# FPGA.net
KiCad netlist of a schematic drawn in Altium Designer
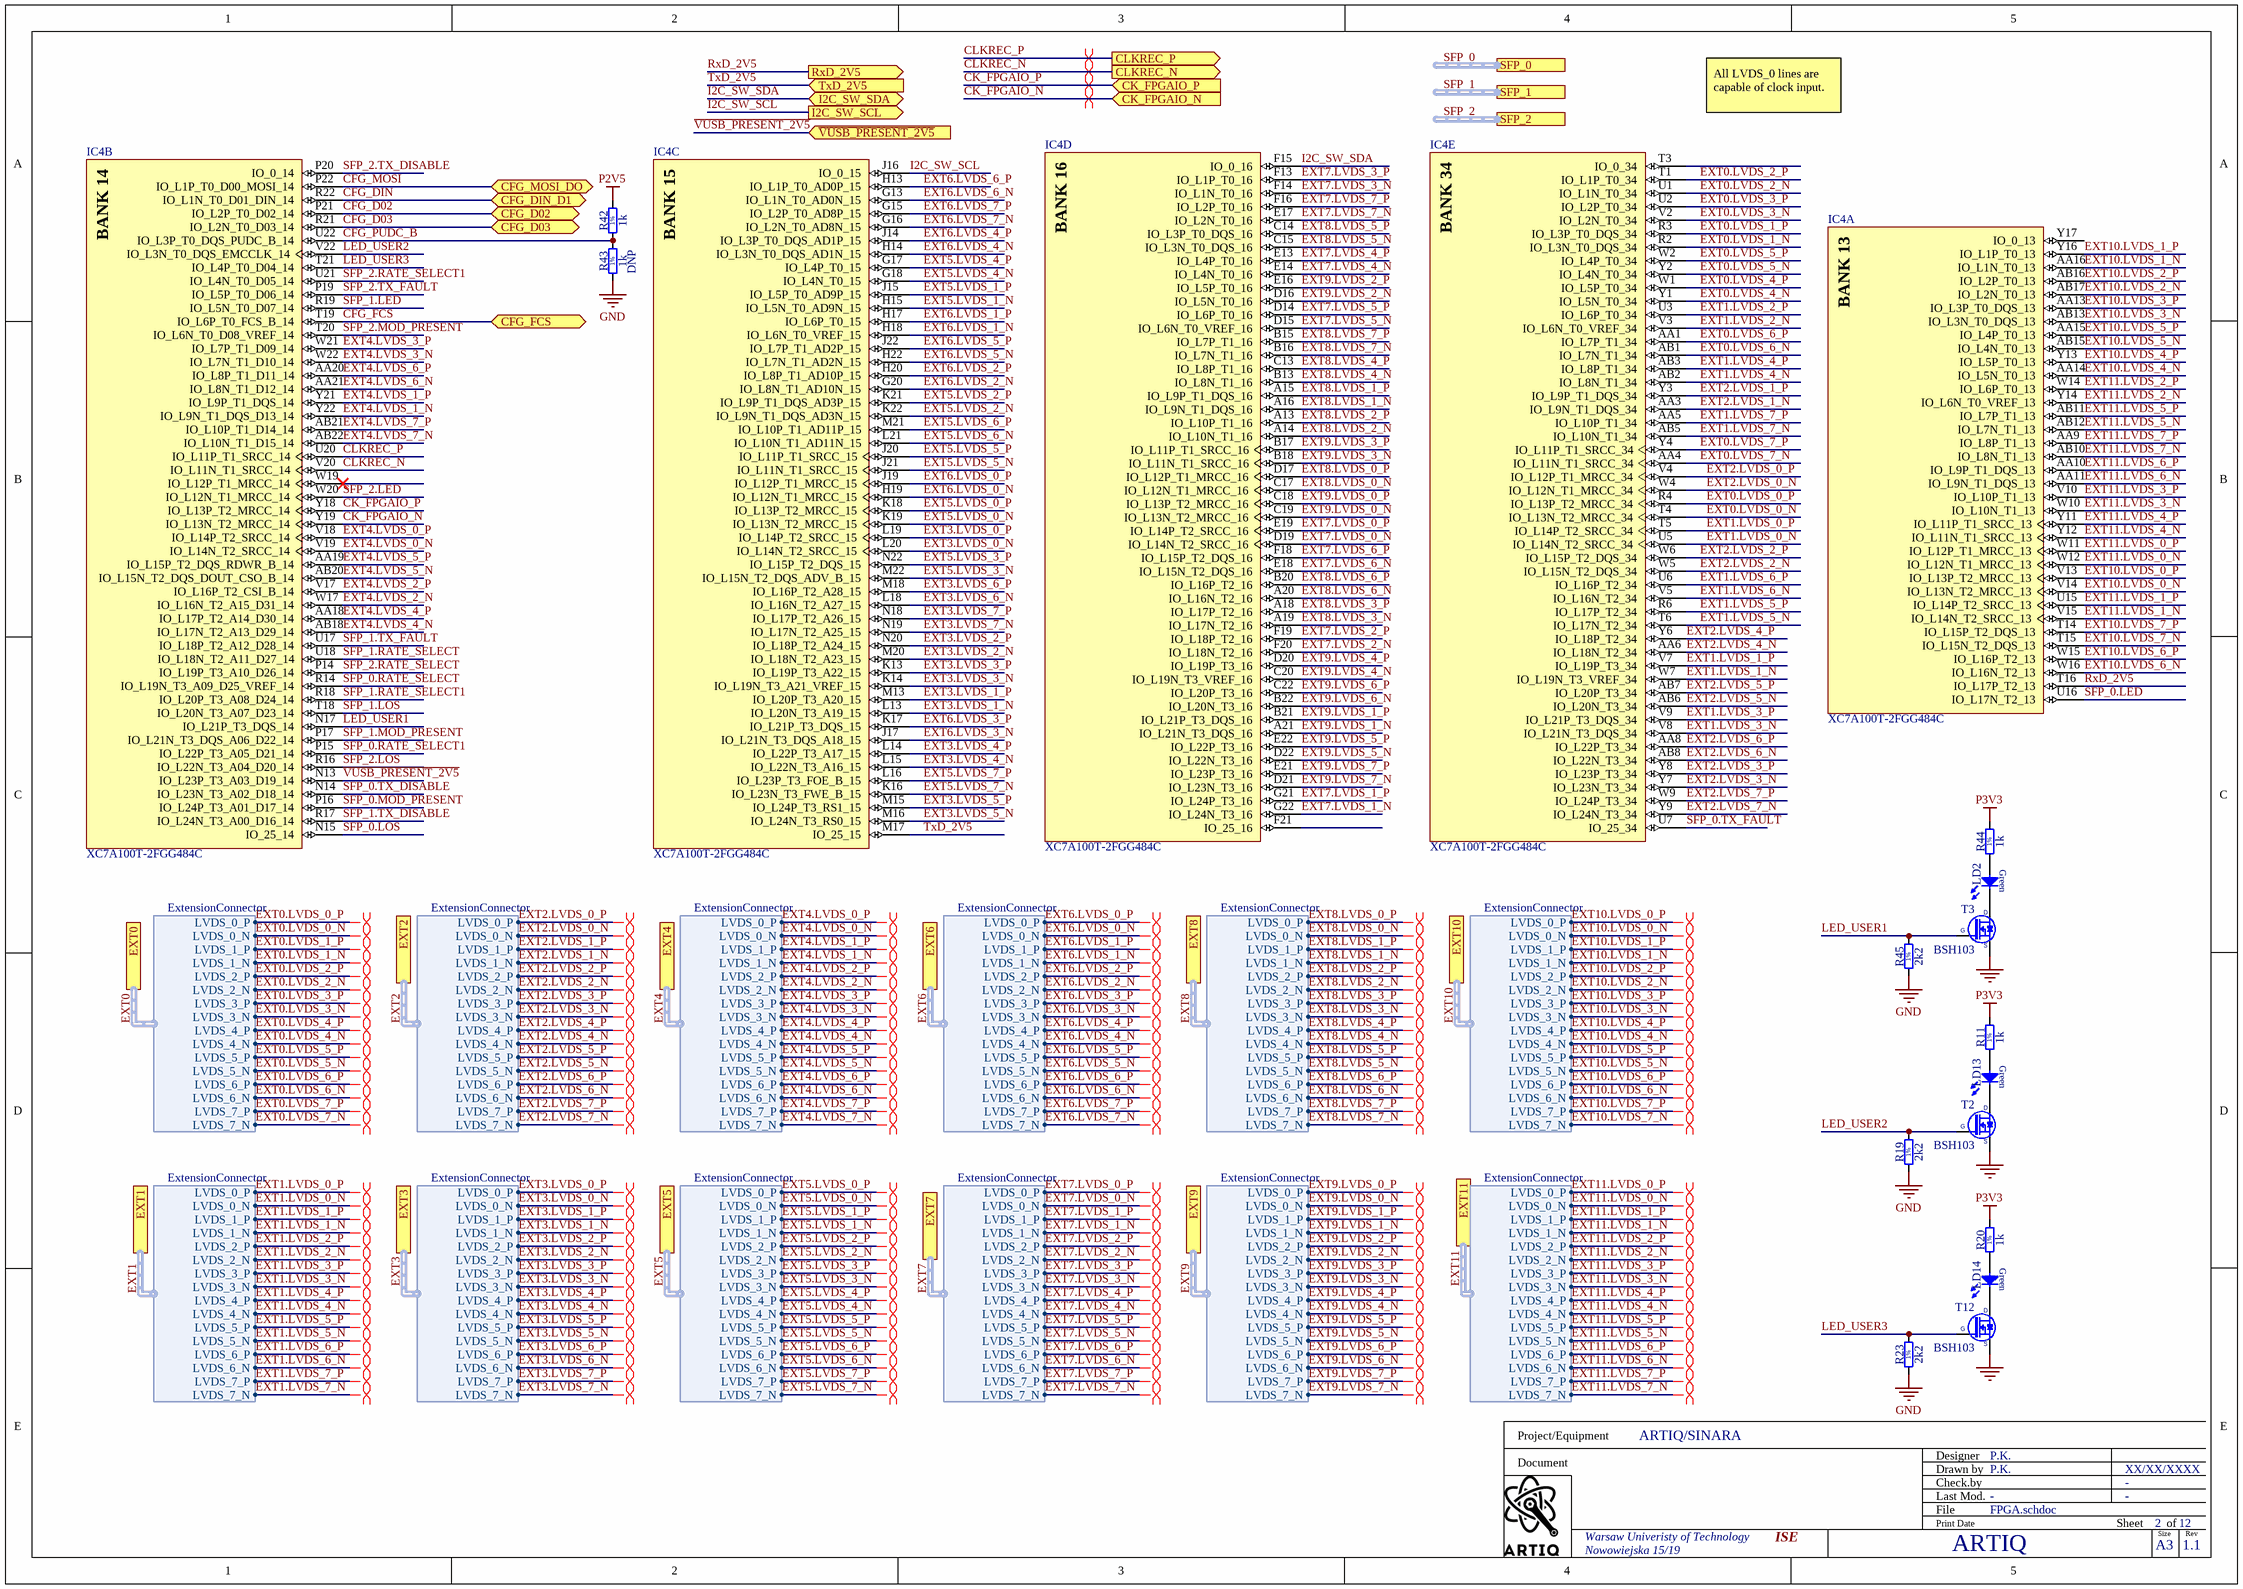
[diagram p0: FPGA.schdoc]

(export (version "E")
  (design (tool "Eeschema 10.0.6"))
  (components
    (comp (ref "IC4")
      (value "XC7A100T-2FGG484C")
      (footprint "FGG484")
      (description "Artix-7 FPGA, 285 User I/Os, 4 GTP, 484-Ball BGA, Speed Grade 2, Commercial Grade, Pb-Free")
      (fields (field (name "GENERIC PART NUMBER") "XC7A100T") (field (name "MANUFACTURER") "Xilinx"))
      (libsource (lib "Altium Content Vault") (part "XC7A100T-2FGG484C"))
    )
    (comp (ref "LD2")
      (value "~")
      (footprint "LED_KINGBRIGHT_KPH-1608CGCK")
      (description "LED Green 1A 2C")
      (fields (field (name "MANUFACTURER PART NUMBER") "KPH-1608CGCK"))
      (libsource (lib "Schlib1") (part "KINGBRIGHT_KPTR-3216CGCK"))
    )
    (comp (ref "LD13")
      (value "~")
      (footprint "LED_KINGBRIGHT_KPH-1608CGCK")
      (description "LED Green 1A 2C")
      (fields (field (name "MANUFACTURER PART NUMBER") "KPH-1608CGCK"))
      (libsource (lib "Schlib1") (part "KINGBRIGHT_KPTR-3216CGCK"))
    )
    (comp (ref "LD14")
      (value "~")
      (footprint "LED_KINGBRIGHT_KPH-1608CGCK")
      (description "LED Green 1A 2C")
      (fields (field (name "MANUFACTURER PART NUMBER") "KPH-1608CGCK"))
      (libsource (lib "Schlib1") (part "KINGBRIGHT_KPTR-3216CGCK"))
    )
    (comp (ref "R11")
      (value "1k")
      (footprint "RESC1005X40N")
      (description "Resistor - 1%")
      (fields
        (field (name "PART NUMBER") "R0402_1K_1%_0.0625W_100PPM")
        (field (name "POWER") "0.0625W")
        (field (name "AUTHOR") "CERN DEM JLC")
      )
      (libsource (lib "Resistors") (part "Resistor - 1%"))
    )
    (comp (ref "R19")
      (value "2k2")
      (footprint "RESC1005X40N")
      (description "Resistor - 1%")
      (fields
        (field (name "PART NUMBER") "R0402_2K2_1%_0.0625W_100PPM")
        (field (name "POWER") "0.0625W")
        (field (name "AUTHOR") "CERN DEM JLC")
      )
      (libsource (lib "Resistors") (part "Resistor - 1%"))
    )
    (comp (ref "R20")
      (value "1k")
      (footprint "RESC1005X40N")
      (description "Resistor - 1%")
      (fields
        (field (name "PART NUMBER") "R0402_1K_1%_0.0625W_100PPM")
        (field (name "POWER") "0.0625W")
        (field (name "AUTHOR") "CERN DEM JLC")
      )
      (libsource (lib "Resistors") (part "Resistor - 1%"))
    )
    (comp (ref "R23")
      (value "2k2")
      (footprint "RESC1005X40N")
      (description "Resistor - 1%")
      (fields
        (field (name "PART NUMBER") "R0402_2K2_1%_0.0625W_100PPM")
        (field (name "POWER") "0.0625W")
        (field (name "AUTHOR") "CERN DEM JLC")
      )
      (libsource (lib "Resistors") (part "Resistor - 1%"))
    )
    (comp (ref "R42")
      (value "1k")
      (footprint "RESC1005X40N")
      (description "Resistor - 1%")
      (fields
        (field (name "PART NUMBER") "R0402_1K_1%_0.0625W_100PPM")
        (field (name "POWER") "0.0625W")
        (field (name "AUTHOR") "CERN DEM JLC")
      )
      (libsource (lib "Resistors") (part "Resistor - 1%"))
    )
    (comp (ref "R43")
      (value "1k")
      (footprint "RESC1005X40N")
      (description "Resistor - 1%")
      (fields
        (field (name "PART NUMBER") "R0402_1K_1%_0.0625W_100PPM")
        (field (name "POWER") "0.0625W")
        (field (name "AUTHOR") "CERN DEM JLC")
      )
      (libsource (lib "Resistors") (part "Resistor - 1%"))
    )
    (comp (ref "R44")
      (value "1k")
      (footprint "RESC1005X40N")
      (description "Resistor - 1%")
      (fields
        (field (name "PART NUMBER") "R0402_1K_1%_0.0625W_100PPM")
        (field (name "POWER") "0.0625W")
        (field (name "AUTHOR") "CERN DEM JLC")
      )
      (libsource (lib "Resistors") (part "Resistor - 1%"))
    )
    (comp (ref "R45")
      (value "2k2")
      (footprint "RESC1005X40N")
      (description "Resistor - 1%")
      (fields
        (field (name "PART NUMBER") "R0402_2K2_1%_0.0625W_100PPM")
        (field (name "POWER") "0.0625W")
        (field (name "AUTHOR") "CERN DEM JLC")
      )
      (libsource (lib "Resistors") (part "Resistor - 1%"))
    )
    (comp (ref "T2")
      (value "BSH103")
      (footprint "SOT95P230X110-3N")
      (description "N-CHANNEL MOSFET WITH DIODE")
      (fields (field (name "MANUFACTURER") "NEXPERIA") (field (name "AUTHOR") "CERN DEM JLC"))
      (libsource (lib "ICs And Semiconductors") (part "N-MOSFET-D 1G 2S 3D"))
    )
    (comp (ref "T3")
      (value "BSH103")
      (footprint "SOT95P230X110-3N")
      (description "N-CHANNEL MOSFET WITH DIODE")
      (fields (field (name "MANUFACTURER") "NEXPERIA") (field (name "AUTHOR") "CERN DEM JLC"))
      (libsource (lib "ICs And Semiconductors") (part "N-MOSFET-D 1G 2S 3D"))
    )
    (comp (ref "T12")
      (value "BSH103")
      (footprint "SOT95P230X110-3N")
      (description "N-CHANNEL MOSFET WITH DIODE")
      (fields (field (name "MANUFACTURER") "NEXPERIA") (field (name "AUTHOR") "CERN DEM JLC"))
      (libsource (lib "ICs And Semiconductors") (part "N-MOSFET-D 1G 2S 3D"))
    )
  )
  (nets
    (net (code "16") (name "/CFG_D02") (class "Default")
      (node (ref "IC4") (pin "P21") (pinfunction "IO_L2P_T0_D02_14_P21") (pintype "bidirectional"))
    )
    (net (code "17") (name "/CFG_D03") (class "Default")
      (node (ref "IC4") (pin "R21") (pinfunction "IO_L2N_T0_D03_14_R21") (pintype "bidirectional"))
    )
    (net (code "18") (name "/CFG_DIN") (class "Default")
      (node (ref "IC4") (pin "R22") (pinfunction "IO_L1N_T0_D01_DIN_14_R22") (pintype "bidirectional"))
    )
    (net (code "19") (name "/CFG_FCS") (class "Default")
      (node (ref "IC4") (pin "T19") (pinfunction "IO_L6P_T0_FCS_B_14_T19") (pintype "bidirectional"))
    )
    (net (code "20") (name "/CFG_MOSI") (class "Default")
      (node (ref "IC4") (pin "P22") (pinfunction "IO_L1P_T0_D00_MOSI_14_P22") (pintype "bidirectional"))
    )
    (net (code "21") (name "/CFG_PUDC_B") (class "Default")
      (node (ref "IC4") (pin "U22") (pinfunction "IO_L3P_T0_DQS_PUDC_B_14_U22") (pintype "bidirectional"))
      (node (ref "R42") (pin "1") (pinfunction "1_1") (pintype "passive"))
      (node (ref "R43") (pin "2") (pinfunction "2_2") (pintype "passive"))
    )
    (net (code "22") (name "/CK_FPGAIO_N") (class "Default")
      (node (ref "IC4") (pin "Y19") (pinfunction "IO_L13N_T2_MRCC_14_Y19") (pintype "bidirectional"))
    )
    (net (code "23") (name "/CK_FPGAIO_P") (class "Default")
      (node (ref "IC4") (pin "Y18") (pinfunction "IO_L13P_T2_MRCC_14_Y18") (pintype "bidirectional"))
    )
    (net (code "24") (name "/CLKREC_N") (class "Default")
      (node (ref "IC4") (pin "V20") (pinfunction "IO_L11N_T1_SRCC_14_V20") (pintype "bidirectional"))
    )
    (net (code "25") (name "/CLKREC_P") (class "Default")
      (node (ref "IC4") (pin "U20") (pinfunction "IO_L11P_T1_SRCC_14_U20") (pintype "bidirectional"))
    )
    (net (code "26") (name "/EXT0.LVDS_0_N") (class "Default")
      (node (ref "IC4") (pin "T4") (pinfunction "IO_L13N_T2_MRCC_34_T4") (pintype "bidirectional"))
    )
    (net (code "27") (name "/EXT0.LVDS_0_P") (class "Default")
      (node (ref "IC4") (pin "R4") (pinfunction "IO_L13P_T2_MRCC_34_R4") (pintype "bidirectional"))
    )
    (net (code "28") (name "/EXT0.LVDS_1_N") (class "Default")
      (node (ref "IC4") (pin "R2") (pinfunction "IO_L3N_T0_DQS_34_R2") (pintype "bidirectional"))
    )
    (net (code "29") (name "/EXT0.LVDS_1_P") (class "Default")
      (node (ref "IC4") (pin "R3") (pinfunction "IO_L3P_T0_DQS_34_R3") (pintype "bidirectional"))
    )
    (net (code "30") (name "/EXT0.LVDS_2_N") (class "Default")
      (node (ref "IC4") (pin "U1") (pinfunction "IO_L1N_T0_34_U1") (pintype "bidirectional"))
    )
    (net (code "31") (name "/EXT0.LVDS_2_P") (class "Default")
      (node (ref "IC4") (pin "T1") (pinfunction "IO_L1P_T0_34_T1") (pintype "bidirectional"))
    )
    (net (code "32") (name "/EXT0.LVDS_3_N") (class "Default")
      (node (ref "IC4") (pin "V2") (pinfunction "IO_L2N_T0_34_V2") (pintype "bidirectional"))
    )
    (net (code "33") (name "/EXT0.LVDS_3_P") (class "Default")
      (node (ref "IC4") (pin "U2") (pinfunction "IO_L2P_T0_34_U2") (pintype "bidirectional"))
    )
    (net (code "34") (name "/EXT0.LVDS_4_N") (class "Default")
      (node (ref "IC4") (pin "Y1") (pinfunction "IO_L5N_T0_34_Y1") (pintype "bidirectional"))
    )
    (net (code "35") (name "/EXT0.LVDS_4_P") (class "Default")
      (node (ref "IC4") (pin "W1") (pinfunction "IO_L5P_T0_34_W1") (pintype "bidirectional"))
    )
    (net (code "36") (name "/EXT0.LVDS_5_N") (class "Default")
      (node (ref "IC4") (pin "Y2") (pinfunction "IO_L4N_T0_34_Y2") (pintype "bidirectional"))
    )
    (net (code "37") (name "/EXT0.LVDS_5_P") (class "Default")
      (node (ref "IC4") (pin "W2") (pinfunction "IO_L4P_T0_34_W2") (pintype "bidirectional"))
    )
    (net (code "38") (name "/EXT0.LVDS_6_N") (class "Default")
      (node (ref "IC4") (pin "AB1") (pinfunction "IO_L7N_T1_34_AB1") (pintype "bidirectional"))
    )
    (net (code "39") (name "/EXT0.LVDS_6_P") (class "Default")
      (node (ref "IC4") (pin "AA1") (pinfunction "IO_L7P_T1_34_AA1") (pintype "bidirectional"))
    )
    (net (code "40") (name "/EXT0.LVDS_7_N") (class "Default")
      (node (ref "IC4") (pin "AA4") (pinfunction "IO_L11N_T1_SRCC_34_AA4") (pintype "bidirectional"))
    )
    (net (code "41") (name "/EXT0.LVDS_7_P") (class "Default")
      (node (ref "IC4") (pin "Y4") (pinfunction "IO_L11P_T1_SRCC_34_Y4") (pintype "bidirectional"))
    )
    (net (code "43") (name "/EXT1.LVDS_0_N") (class "Default")
      (node (ref "IC4") (pin "U5") (pinfunction "IO_L14N_T2_SRCC_34_U5") (pintype "bidirectional"))
    )
    (net (code "44") (name "/EXT1.LVDS_0_P") (class "Default")
      (node (ref "IC4") (pin "T5") (pinfunction "IO_L14P_T2_SRCC_34_T5") (pintype "bidirectional"))
    )
    (net (code "45") (name "/EXT1.LVDS_1_N") (class "Default")
      (node (ref "IC4") (pin "W7") (pinfunction "IO_L19N_T3_VREF_34_W7") (pintype "bidirectional"))
    )
    (net (code "46") (name "/EXT1.LVDS_1_P") (class "Default")
      (node (ref "IC4") (pin "V7") (pinfunction "IO_L19P_T3_34_V7") (pintype "bidirectional"))
    )
    (net (code "47") (name "/EXT1.LVDS_2_N") (class "Default")
      (node (ref "IC4") (pin "V3") (pinfunction "IO_L6N_T0_VREF_34_V3") (pintype "bidirectional"))
    )
    (net (code "48") (name "/EXT1.LVDS_2_P") (class "Default")
      (node (ref "IC4") (pin "U3") (pinfunction "IO_L6P_T0_34_U3") (pintype "bidirectional"))
    )
    (net (code "49") (name "/EXT1.LVDS_3_N") (class "Default")
      (node (ref "IC4") (pin "V8") (pinfunction "IO_L21N_T3_DQS_34_V8") (pintype "bidirectional"))
    )
    (net (code "50") (name "/EXT1.LVDS_3_P") (class "Default")
      (node (ref "IC4") (pin "V9") (pinfunction "IO_L21P_T3_DQS_34_V9") (pintype "bidirectional"))
    )
    (net (code "51") (name "/EXT1.LVDS_4_N") (class "Default")
      (node (ref "IC4") (pin "AB2") (pinfunction "IO_L8N_T1_34_AB2") (pintype "bidirectional"))
    )
    (net (code "52") (name "/EXT1.LVDS_4_P") (class "Default")
      (node (ref "IC4") (pin "AB3") (pinfunction "IO_L8P_T1_34_AB3") (pintype "bidirectional"))
    )
    (net (code "53") (name "/EXT1.LVDS_5_N") (class "Default")
      (node (ref "IC4") (pin "T6") (pinfunction "IO_L17N_T2_34_T6") (pintype "bidirectional"))
    )
    (net (code "54") (name "/EXT1.LVDS_5_P") (class "Default")
      (node (ref "IC4") (pin "R6") (pinfunction "IO_L17P_T2_34_R6") (pintype "bidirectional"))
    )
    (net (code "55") (name "/EXT1.LVDS_6_N") (class "Default")
      (node (ref "IC4") (pin "V5") (pinfunction "IO_L16N_T2_34_V5") (pintype "bidirectional"))
    )
    (net (code "56") (name "/EXT1.LVDS_6_P") (class "Default")
      (node (ref "IC4") (pin "U6") (pinfunction "IO_L16P_T2_34_U6") (pintype "bidirectional"))
    )
    (net (code "57") (name "/EXT1.LVDS_7_N") (class "Default")
      (node (ref "IC4") (pin "AB5") (pinfunction "IO_L10N_T1_34_AB5") (pintype "bidirectional"))
    )
    (net (code "58") (name "/EXT1.LVDS_7_P") (class "Default")
      (node (ref "IC4") (pin "AA5") (pinfunction "IO_L10P_T1_34_AA5") (pintype "bidirectional"))
    )
    (net (code "60") (name "/EXT2.LVDS_0_N") (class "Default")
      (node (ref "IC4") (pin "W4") (pinfunction "IO_L12N_T1_MRCC_34_W4") (pintype "bidirectional"))
    )
    (net (code "61") (name "/EXT2.LVDS_0_P") (class "Default")
      (node (ref "IC4") (pin "V4") (pinfunction "IO_L12P_T1_MRCC_34_V4") (pintype "bidirectional"))
    )
    (net (code "62") (name "/EXT2.LVDS_1_N") (class "Default")
      (node (ref "IC4") (pin "AA3") (pinfunction "IO_L9N_T1_DQS_34_AA3") (pintype "bidirectional"))
    )
    (net (code "63") (name "/EXT2.LVDS_1_P") (class "Default")
      (node (ref "IC4") (pin "Y3") (pinfunction "IO_L9P_T1_DQS_34_Y3") (pintype "bidirectional"))
    )
    (net (code "64") (name "/EXT2.LVDS_2_N") (class "Default")
      (node (ref "IC4") (pin "W5") (pinfunction "IO_L15N_T2_DQS_34_W5") (pintype "bidirectional"))
    )
    (net (code "65") (name "/EXT2.LVDS_2_P") (class "Default")
      (node (ref "IC4") (pin "W6") (pinfunction "IO_L15P_T2_DQS_34_W6") (pintype "bidirectional"))
    )
    (net (code "66") (name "/EXT2.LVDS_3_N") (class "Default")
      (node (ref "IC4") (pin "Y7") (pinfunction "IO_L23N_T3_34_Y7") (pintype "bidirectional"))
    )
    (net (code "67") (name "/EXT2.LVDS_3_P") (class "Default")
      (node (ref "IC4") (pin "Y8") (pinfunction "IO_L23P_T3_34_Y8") (pintype "bidirectional"))
    )
    (net (code "68") (name "/EXT2.LVDS_4_N") (class "Default")
      (node (ref "IC4") (pin "AA6") (pinfunction "IO_L18N_T2_34_AA6") (pintype "bidirectional"))
    )
    (net (code "69") (name "/EXT2.LVDS_4_P") (class "Default")
      (node (ref "IC4") (pin "Y6") (pinfunction "IO_L18P_T2_34_Y6") (pintype "bidirectional"))
    )
    (net (code "70") (name "/EXT2.LVDS_5_N") (class "Default")
      (node (ref "IC4") (pin "AB6") (pinfunction "IO_L20N_T3_34_AB6") (pintype "bidirectional"))
    )
    (net (code "71") (name "/EXT2.LVDS_5_P") (class "Default")
      (node (ref "IC4") (pin "AB7") (pinfunction "IO_L20P_T3_34_AB7") (pintype "bidirectional"))
    )
    (net (code "72") (name "/EXT2.LVDS_6_N") (class "Default")
      (node (ref "IC4") (pin "AB8") (pinfunction "IO_L22N_T3_34_AB8") (pintype "bidirectional"))
    )
    (net (code "73") (name "/EXT2.LVDS_6_P") (class "Default")
      (node (ref "IC4") (pin "AA8") (pinfunction "IO_L22P_T3_34_AA8") (pintype "bidirectional"))
    )
    (net (code "74") (name "/EXT2.LVDS_7_N") (class "Default")
      (node (ref "IC4") (pin "Y9") (pinfunction "IO_L24N_T3_34_Y9") (pintype "bidirectional"))
    )
    (net (code "75") (name "/EXT2.LVDS_7_P") (class "Default")
      (node (ref "IC4") (pin "W9") (pinfunction "IO_L24P_T3_34_W9") (pintype "bidirectional"))
    )
    (net (code "77") (name "/EXT3.LVDS_0_N") (class "Default")
      (node (ref "IC4") (pin "L20") (pinfunction "IO_L14N_T2_SRCC_15_L20") (pintype "bidirectional"))
    )
    (net (code "78") (name "/EXT3.LVDS_0_P") (class "Default")
      (node (ref "IC4") (pin "L19") (pinfunction "IO_L14P_T2_SRCC_15_L19") (pintype "bidirectional"))
    )
    (net (code "79") (name "/EXT3.LVDS_1_N") (class "Default")
      (node (ref "IC4") (pin "L13") (pinfunction "IO_L20N_T3_A19_15_L13") (pintype "bidirectional"))
    )
    (net (code "80") (name "/EXT3.LVDS_1_P") (class "Default")
      (node (ref "IC4") (pin "M13") (pinfunction "IO_L20P_T3_A20_15_M13") (pintype "bidirectional"))
    )
    (net (code "81") (name "/EXT3.LVDS_2_N") (class "Default")
      (node (ref "IC4") (pin "M20") (pinfunction "IO_L18N_T2_A23_15_M20") (pintype "bidirectional"))
    )
    (net (code "82") (name "/EXT3.LVDS_2_P") (class "Default")
      (node (ref "IC4") (pin "N20") (pinfunction "IO_L18P_T2_A24_15_N20") (pintype "bidirectional"))
    )
    (net (code "83") (name "/EXT3.LVDS_3_N") (class "Default")
      (node (ref "IC4") (pin "K14") (pinfunction "IO_L19N_T3_A21_VREF_15_K14") (pintype "bidirectional"))
    )
    (net (code "84") (name "/EXT3.LVDS_3_P") (class "Default")
      (node (ref "IC4") (pin "K13") (pinfunction "IO_L19P_T3_A22_15_K13") (pintype "bidirectional"))
    )
    (net (code "85") (name "/EXT3.LVDS_4_N") (class "Default")
      (node (ref "IC4") (pin "L15") (pinfunction "IO_L22N_T3_A16_15_L15") (pintype "bidirectional"))
    )
    (net (code "86") (name "/EXT3.LVDS_4_P") (class "Default")
      (node (ref "IC4") (pin "L14") (pinfunction "IO_L22P_T3_A17_15_L14") (pintype "bidirectional"))
    )
    (net (code "87") (name "/EXT3.LVDS_5_N") (class "Default")
      (node (ref "IC4") (pin "M16") (pinfunction "IO_L24N_T3_RS0_15_M16") (pintype "bidirectional"))
    )
    (net (code "88") (name "/EXT3.LVDS_5_P") (class "Default")
      (node (ref "IC4") (pin "M15") (pinfunction "IO_L24P_T3_RS1_15_M15") (pintype "bidirectional"))
    )
    (net (code "89") (name "/EXT3.LVDS_6_N") (class "Default")
      (node (ref "IC4") (pin "L18") (pinfunction "IO_L16N_T2_A27_15_L18") (pintype "bidirectional"))
    )
    (net (code "90") (name "/EXT3.LVDS_6_P") (class "Default")
      (node (ref "IC4") (pin "M18") (pinfunction "IO_L16P_T2_A28_15_M18") (pintype "bidirectional"))
    )
    (net (code "91") (name "/EXT3.LVDS_7_N") (class "Default")
      (node (ref "IC4") (pin "N19") (pinfunction "IO_L17N_T2_A25_15_N19") (pintype "bidirectional"))
    )
    (net (code "92") (name "/EXT3.LVDS_7_P") (class "Default")
      (node (ref "IC4") (pin "N18") (pinfunction "IO_L17P_T2_A26_15_N18") (pintype "bidirectional"))
    )
    (net (code "94") (name "/EXT4.LVDS_0_N") (class "Default")
      (node (ref "IC4") (pin "V19") (pinfunction "IO_L14N_T2_SRCC_14_V19") (pintype "bidirectional"))
    )
    (net (code "95") (name "/EXT4.LVDS_0_P") (class "Default")
      (node (ref "IC4") (pin "V18") (pinfunction "IO_L14P_T2_SRCC_14_V18") (pintype "bidirectional"))
    )
    (net (code "96") (name "/EXT4.LVDS_1_N") (class "Default")
      (node (ref "IC4") (pin "Y22") (pinfunction "IO_L9N_T1_DQS_D13_14_Y22") (pintype "bidirectional"))
    )
    (net (code "97") (name "/EXT4.LVDS_1_P") (class "Default")
      (node (ref "IC4") (pin "Y21") (pinfunction "IO_L9P_T1_DQS_14_Y21") (pintype "bidirectional"))
    )
    (net (code "98") (name "/EXT4.LVDS_2_N") (class "Default")
      (node (ref "IC4") (pin "W17") (pinfunction "IO_L16N_T2_A15_D31_14_W17") (pintype "bidirectional"))
    )
    (net (code "99") (name "/EXT4.LVDS_2_P") (class "Default")
      (node (ref "IC4") (pin "V17") (pinfunction "IO_L16P_T2_CSI_B_14_V17") (pintype "bidirectional"))
    )
    (net (code "100") (name "/EXT4.LVDS_3_N") (class "Default")
      (node (ref "IC4") (pin "W22") (pinfunction "IO_L7N_T1_D10_14_W22") (pintype "bidirectional"))
    )
    (net (code "101") (name "/EXT4.LVDS_3_P") (class "Default")
      (node (ref "IC4") (pin "W21") (pinfunction "IO_L7P_T1_D09_14_W21") (pintype "bidirectional"))
    )
    (net (code "102") (name "/EXT4.LVDS_4_N") (class "Default")
      (node (ref "IC4") (pin "AB18") (pinfunction "IO_L17N_T2_A13_D29_14_AB18") (pintype "bidirectional"))
    )
    (net (code "103") (name "/EXT4.LVDS_4_P") (class "Default")
      (node (ref "IC4") (pin "AA18") (pinfunction "IO_L17P_T2_A14_D30_14_AA18") (pintype "bidirectional"))
    )
    (net (code "104") (name "/EXT4.LVDS_5_N") (class "Default")
      (node (ref "IC4") (pin "AB20") (pinfunction "IO_L15N_T2_DQS_DOUT_CSO_B_14_AB20") (pintype "bidirectional"))
    )
    (net (code "105") (name "/EXT4.LVDS_5_P") (class "Default")
      (node (ref "IC4") (pin "AA19") (pinfunction "IO_L15P_T2_DQS_RDWR_B_14_AA19") (pintype "bidirectional"))
    )
    (net (code "106") (name "/EXT4.LVDS_6_N") (class "Default")
      (node (ref "IC4") (pin "AA21") (pinfunction "IO_L8N_T1_D12_14_AA21") (pintype "bidirectional"))
    )
    (net (code "107") (name "/EXT4.LVDS_6_P") (class "Default")
      (node (ref "IC4") (pin "AA20") (pinfunction "IO_L8P_T1_D11_14_AA20") (pintype "bidirectional"))
    )
    (net (code "108") (name "/EXT4.LVDS_7_N") (class "Default")
      (node (ref "IC4") (pin "AB22") (pinfunction "IO_L10N_T1_D15_14_AB22") (pintype "bidirectional"))
    )
    (net (code "109") (name "/EXT4.LVDS_7_P") (class "Default")
      (node (ref "IC4") (pin "AB21") (pinfunction "IO_L10P_T1_D14_14_AB21") (pintype "bidirectional"))
    )
    (net (code "111") (name "/EXT5.LVDS_0_N") (class "Default")
      (node (ref "IC4") (pin "K19") (pinfunction "IO_L13N_T2_MRCC_15_K19") (pintype "bidirectional"))
    )
    (net (code "112") (name "/EXT5.LVDS_0_P") (class "Default")
      (node (ref "IC4") (pin "K18") (pinfunction "IO_L13P_T2_MRCC_15_K18") (pintype "bidirectional"))
    )
    (net (code "113") (name "/EXT5.LVDS_1_N") (class "Default")
      (node (ref "IC4") (pin "H15") (pinfunction "IO_L5N_T0_AD9N_15_H15") (pintype "bidirectional"))
    )
    (net (code "114") (name "/EXT5.LVDS_1_P") (class "Default")
      (node (ref "IC4") (pin "J15") (pinfunction "IO_L5P_T0_AD9P_15_J15") (pintype "bidirectional"))
    )
    (net (code "115") (name "/EXT5.LVDS_2_N") (class "Default")
      (node (ref "IC4") (pin "K22") (pinfunction "IO_L9N_T1_DQS_AD3N_15_K22") (pintype "bidirectional"))
    )
    (net (code "116") (name "/EXT5.LVDS_2_P") (class "Default")
      (node (ref "IC4") (pin "K21") (pinfunction "IO_L9P_T1_DQS_AD3P_15_K21") (pintype "bidirectional"))
    )
    (net (code "117") (name "/EXT5.LVDS_3_N") (class "Default")
      (node (ref "IC4") (pin "M22") (pinfunction "IO_L15N_T2_DQS_ADV_B_15_M22") (pintype "bidirectional"))
    )
    (net (code "118") (name "/EXT5.LVDS_3_P") (class "Default")
      (node (ref "IC4") (pin "N22") (pinfunction "IO_L15P_T2_DQS_15_N22") (pintype "bidirectional"))
    )
    (net (code "119") (name "/EXT5.LVDS_4_N") (class "Default")
      (node (ref "IC4") (pin "G18") (pinfunction "IO_L4N_T0_15_G18") (pintype "bidirectional"))
    )
    (net (code "120") (name "/EXT5.LVDS_4_P") (class "Default")
      (node (ref "IC4") (pin "G17") (pinfunction "IO_L4P_T0_15_G17") (pintype "bidirectional"))
    )
    (net (code "121") (name "/EXT5.LVDS_5_N") (class "Default")
      (node (ref "IC4") (pin "J21") (pinfunction "IO_L11N_T1_SRCC_15_J21") (pintype "bidirectional"))
    )
    (net (code "122") (name "/EXT5.LVDS_5_P") (class "Default")
      (node (ref "IC4") (pin "J20") (pinfunction "IO_L11P_T1_SRCC_15_J20") (pintype "bidirectional"))
    )
    (net (code "123") (name "/EXT5.LVDS_6_N") (class "Default")
      (node (ref "IC4") (pin "L21") (pinfunction "IO_L10N_T1_AD11N_15_L21") (pintype "bidirectional"))
    )
    (net (code "124") (name "/EXT5.LVDS_6_P") (class "Default")
      (node (ref "IC4") (pin "M21") (pinfunction "IO_L10P_T1_AD11P_15_M21") (pintype "bidirectional"))
    )
    (net (code "125") (name "/EXT5.LVDS_7_N") (class "Default")
      (node (ref "IC4") (pin "K16") (pinfunction "IO_L23N_T3_FWE_B_15_K16") (pintype "bidirectional"))
    )
    (net (code "126") (name "/EXT5.LVDS_7_P") (class "Default")
      (node (ref "IC4") (pin "L16") (pinfunction "IO_L23P_T3_FOE_B_15_L16") (pintype "bidirectional"))
    )
    (net (code "128") (name "/EXT6.LVDS_0_N") (class "Default")
      (node (ref "IC4") (pin "H19") (pinfunction "IO_L12N_T1_MRCC_15_H19") (pintype "bidirectional"))
    )
    (net (code "129") (name "/EXT6.LVDS_0_P") (class "Default")
      (node (ref "IC4") (pin "J19") (pinfunction "IO_L12P_T1_MRCC_15_J19") (pintype "bidirectional"))
    )
    (net (code "130") (name "/EXT6.LVDS_1_N") (class "Default")
      (node (ref "IC4") (pin "H18") (pinfunction "IO_L6N_T0_VREF_15_H18") (pintype "bidirectional"))
    )
    (net (code "131") (name "/EXT6.LVDS_1_P") (class "Default")
      (node (ref "IC4") (pin "H17") (pinfunction "IO_L6P_T0_15_H17") (pintype "bidirectional"))
    )
    (net (code "132") (name "/EXT6.LVDS_2_N") (class "Default")
      (node (ref "IC4") (pin "G20") (pinfunction "IO_L8N_T1_AD10N_15_G20") (pintype "bidirectional"))
    )
    (net (code "133") (name "/EXT6.LVDS_2_P") (class "Default")
      (node (ref "IC4") (pin "H20") (pinfunction "IO_L8P_T1_AD10P_15_H20") (pintype "bidirectional"))
    )
    (net (code "134") (name "/EXT6.LVDS_3_N") (class "Default")
      (node (ref "IC4") (pin "J17") (pinfunction "IO_L21N_T3_DQS_A18_15_J17") (pintype "bidirectional"))
    )
    (net (code "135") (name "/EXT6.LVDS_3_P") (class "Default")
      (node (ref "IC4") (pin "K17") (pinfunction "IO_L21P_T3_DQS_15_K17") (pintype "bidirectional"))
    )
    (net (code "136") (name "/EXT6.LVDS_4_N") (class "Default")
      (node (ref "IC4") (pin "H14") (pinfunction "IO_L3N_T0_DQS_AD1N_15_H14") (pintype "bidirectional"))
    )
    (net (code "137") (name "/EXT6.LVDS_4_P") (class "Default")
      (node (ref "IC4") (pin "J14") (pinfunction "IO_L3P_T0_DQS_AD1P_15_J14") (pintype "bidirectional"))
    )
    (net (code "138") (name "/EXT6.LVDS_5_N") (class "Default")
      (node (ref "IC4") (pin "H22") (pinfunction "IO_L7N_T1_AD2N_15_H22") (pintype "bidirectional"))
    )
    (net (code "139") (name "/EXT6.LVDS_5_P") (class "Default")
      (node (ref "IC4") (pin "J22") (pinfunction "IO_L7P_T1_AD2P_15_J22") (pintype "bidirectional"))
    )
    (net (code "140") (name "/EXT6.LVDS_6_N") (class "Default")
      (node (ref "IC4") (pin "G13") (pinfunction "IO_L1N_T0_AD0N_15_G13") (pintype "bidirectional"))
    )
    (net (code "141") (name "/EXT6.LVDS_6_P") (class "Default")
      (node (ref "IC4") (pin "H13") (pinfunction "IO_L1P_T0_AD0P_15_H13") (pintype "bidirectional"))
    )
    (net (code "142") (name "/EXT6.LVDS_7_N") (class "Default")
      (node (ref "IC4") (pin "G16") (pinfunction "IO_L2N_T0_AD8N_15_G16") (pintype "bidirectional"))
    )
    (net (code "143") (name "/EXT6.LVDS_7_P") (class "Default")
      (node (ref "IC4") (pin "G15") (pinfunction "IO_L2P_T0_AD8P_15_G15") (pintype "bidirectional"))
    )
    (net (code "145") (name "/EXT7.LVDS_0_N") (class "Default")
      (node (ref "IC4") (pin "D19") (pinfunction "IO_L14N_T2_SRCC_16_D19") (pintype "bidirectional"))
    )
    (net (code "146") (name "/EXT7.LVDS_0_P") (class "Default")
      (node (ref "IC4") (pin "E19") (pinfunction "IO_L14P_T2_SRCC_16_E19") (pintype "bidirectional"))
    )
    (net (code "147") (name "/EXT7.LVDS_1_N") (class "Default")
      (node (ref "IC4") (pin "G22") (pinfunction "IO_L24N_T3_16_G22") (pintype "bidirectional"))
    )
    (net (code "148") (name "/EXT7.LVDS_1_P") (class "Default")
      (node (ref "IC4") (pin "G21") (pinfunction "IO_L24P_T3_16_G21") (pintype "bidirectional"))
    )
    (net (code "149") (name "/EXT7.LVDS_2_N") (class "Default")
      (node (ref "IC4") (pin "F20") (pinfunction "IO_L18N_T2_16_F20") (pintype "bidirectional"))
    )
    (net (code "150") (name "/EXT7.LVDS_2_P") (class "Default")
      (node (ref "IC4") (pin "F19") (pinfunction "IO_L18P_T2_16_F19") (pintype "bidirectional"))
    )
    (net (code "151") (name "/EXT7.LVDS_3_N") (class "Default")
      (node (ref "IC4") (pin "F14") (pinfunction "IO_L1N_T0_16_F14") (pintype "bidirectional"))
    )
    (net (code "152") (name "/EXT7.LVDS_3_P") (class "Default")
      (node (ref "IC4") (pin "F13") (pinfunction "IO_L1P_T0_16_F13") (pintype "bidirectional"))
    )
    (net (code "153") (name "/EXT7.LVDS_4_N") (class "Default")
      (node (ref "IC4") (pin "E14") (pinfunction "IO_L4N_T0_16_E14") (pintype "bidirectional"))
    )
    (net (code "154") (name "/EXT7.LVDS_4_P") (class "Default")
      (node (ref "IC4") (pin "E13") (pinfunction "IO_L4P_T0_16_E13") (pintype "bidirectional"))
    )
    (net (code "155") (name "/EXT7.LVDS_5_N") (class "Default")
      (node (ref "IC4") (pin "D15") (pinfunction "IO_L6N_T0_VREF_16_D15") (pintype "bidirectional"))
    )
    (net (code "156") (name "/EXT7.LVDS_5_P") (class "Default")
      (node (ref "IC4") (pin "D14") (pinfunction "IO_L6P_T0_16_D14") (pintype "bidirectional"))
    )
    (net (code "157") (name "/EXT7.LVDS_6_N") (class "Default")
      (node (ref "IC4") (pin "E18") (pinfunction "IO_L15N_T2_DQS_16_E18") (pintype "bidirectional"))
    )
    (net (code "158") (name "/EXT7.LVDS_6_P") (class "Default")
      (node (ref "IC4") (pin "F18") (pinfunction "IO_L15P_T2_DQS_16_F18") (pintype "bidirectional"))
    )
    (net (code "159") (name "/EXT7.LVDS_7_N") (class "Default")
      (node (ref "IC4") (pin "E17") (pinfunction "IO_L2N_T0_16_E17") (pintype "bidirectional"))
    )
    (net (code "160") (name "/EXT7.LVDS_7_P") (class "Default")
      (node (ref "IC4") (pin "F16") (pinfunction "IO_L2P_T0_16_F16") (pintype "bidirectional"))
    )
    (net (code "162") (name "/EXT8.LVDS_0_N") (class "Default")
      (node (ref "IC4") (pin "C17") (pinfunction "IO_L12N_T1_MRCC_16_C17") (pintype "bidirectional"))
    )
    (net (code "163") (name "/EXT8.LVDS_0_P") (class "Default")
      (node (ref "IC4") (pin "D17") (pinfunction "IO_L12P_T1_MRCC_16_D17") (pintype "bidirectional"))
    )
    (net (code "164") (name "/EXT8.LVDS_1_N") (class "Default")
      (node (ref "IC4") (pin "A16") (pinfunction "IO_L9N_T1_DQS_16_A16") (pintype "bidirectional"))
    )
    (net (code "165") (name "/EXT8.LVDS_1_P") (class "Default")
      (node (ref "IC4") (pin "A15") (pinfunction "IO_L9P_T1_DQS_16_A15") (pintype "bidirectional"))
    )
    (net (code "166") (name "/EXT8.LVDS_2_N") (class "Default")
      (node (ref "IC4") (pin "A14") (pinfunction "IO_L10N_T1_16_A14") (pintype "bidirectional"))
    )
    (net (code "167") (name "/EXT8.LVDS_2_P") (class "Default")
      (node (ref "IC4") (pin "A13") (pinfunction "IO_L10P_T1_16_A13") (pintype "bidirectional"))
    )
    (net (code "168") (name "/EXT8.LVDS_3_N") (class "Default")
      (node (ref "IC4") (pin "A19") (pinfunction "IO_L17N_T2_16_A19") (pintype "bidirectional"))
    )
    (net (code "169") (name "/EXT8.LVDS_3_P") (class "Default")
      (node (ref "IC4") (pin "A18") (pinfunction "IO_L17P_T2_16_A18") (pintype "bidirectional"))
    )
    (net (code "170") (name "/EXT8.LVDS_4_N") (class "Default")
      (node (ref "IC4") (pin "B13") (pinfunction "IO_L8N_T1_16_B13") (pintype "bidirectional"))
    )
    (net (code "171") (name "/EXT8.LVDS_4_P") (class "Default")
      (node (ref "IC4") (pin "C13") (pinfunction "IO_L8P_T1_16_C13") (pintype "bidirectional"))
    )
    (net (code "172") (name "/EXT8.LVDS_5_N") (class "Default")
      (node (ref "IC4") (pin "C15") (pinfunction "IO_L3N_T0_DQS_16_C15") (pintype "bidirectional"))
    )
    (net (code "173") (name "/EXT8.LVDS_5_P") (class "Default")
      (node (ref "IC4") (pin "C14") (pinfunction "IO_L3P_T0_DQS_16_C14") (pintype "bidirectional"))
    )
    (net (code "174") (name "/EXT8.LVDS_6_N") (class "Default")
      (node (ref "IC4") (pin "A20") (pinfunction "IO_L16N_T2_16_A20") (pintype "bidirectional"))
    )
    (net (code "175") (name "/EXT8.LVDS_6_P") (class "Default")
      (node (ref "IC4") (pin "B20") (pinfunction "IO_L16P_T2_16_B20") (pintype "bidirectional"))
    )
    (net (code "176") (name "/EXT8.LVDS_7_N") (class "Default")
      (node (ref "IC4") (pin "B16") (pinfunction "IO_L7N_T1_16_B16") (pintype "bidirectional"))
    )
    (net (code "177") (name "/EXT8.LVDS_7_P") (class "Default")
      (node (ref "IC4") (pin "B15") (pinfunction "IO_L7P_T1_16_B15") (pintype "bidirectional"))
    )
    (net (code "179") (name "/EXT9.LVDS_0_N") (class "Default")
      (node (ref "IC4") (pin "C19") (pinfunction "IO_L13N_T2_MRCC_16_C19") (pintype "bidirectional"))
    )
    (net (code "180") (name "/EXT9.LVDS_0_P") (class "Default")
      (node (ref "IC4") (pin "C18") (pinfunction "IO_L13P_T2_MRCC_16_C18") (pintype "bidirectional"))
    )
    (net (code "181") (name "/EXT9.LVDS_1_N") (class "Default")
      (node (ref "IC4") (pin "A21") (pinfunction "IO_L21N_T3_DQS_16_A21") (pintype "bidirectional"))
    )
    (net (code "182") (name "/EXT9.LVDS_1_P") (class "Default")
      (node (ref "IC4") (pin "B21") (pinfunction "IO_L21P_T3_DQS_16_B21") (pintype "bidirectional"))
    )
    (net (code "183") (name "/EXT9.LVDS_2_N") (class "Default")
      (node (ref "IC4") (pin "D16") (pinfunction "IO_L5N_T0_16_D16") (pintype "bidirectional"))
    )
    (net (code "184") (name "/EXT9.LVDS_2_P") (class "Default")
      (node (ref "IC4") (pin "E16") (pinfunction "IO_L5P_T0_16_E16") (pintype "bidirectional"))
    )
    (net (code "185") (name "/EXT9.LVDS_3_N") (class "Default")
      (node (ref "IC4") (pin "B18") (pinfunction "IO_L11N_T1_SRCC_16_B18") (pintype "bidirectional"))
    )
    (net (code "186") (name "/EXT9.LVDS_3_P") (class "Default")
      (node (ref "IC4") (pin "B17") (pinfunction "IO_L11P_T1_SRCC_16_B17") (pintype "bidirectional"))
    )
    (net (code "187") (name "/EXT9.LVDS_4_N") (class "Default")
      (node (ref "IC4") (pin "C20") (pinfunction "IO_L19N_T3_VREF_16_C20") (pintype "bidirectional"))
    )
    (net (code "188") (name "/EXT9.LVDS_4_P") (class "Default")
      (node (ref "IC4") (pin "D20") (pinfunction "IO_L19P_T3_16_D20") (pintype "bidirectional"))
    )
    (net (code "189") (name "/EXT9.LVDS_5_N") (class "Default")
      (node (ref "IC4") (pin "D22") (pinfunction "IO_L22N_T3_16_D22") (pintype "bidirectional"))
    )
    (net (code "190") (name "/EXT9.LVDS_5_P") (class "Default")
      (node (ref "IC4") (pin "E22") (pinfunction "IO_L22P_T3_16_E22") (pintype "bidirectional"))
    )
    (net (code "191") (name "/EXT9.LVDS_6_N") (class "Default")
      (node (ref "IC4") (pin "B22") (pinfunction "IO_L20N_T3_16_B22") (pintype "bidirectional"))
    )
    (net (code "192") (name "/EXT9.LVDS_6_P") (class "Default")
      (node (ref "IC4") (pin "C22") (pinfunction "IO_L20P_T3_16_C22") (pintype "bidirectional"))
    )
    (net (code "193") (name "/EXT9.LVDS_7_N") (class "Default")
      (node (ref "IC4") (pin "D21") (pinfunction "IO_L23N_T3_16_D21") (pintype "bidirectional"))
    )
    (net (code "194") (name "/EXT9.LVDS_7_P") (class "Default")
      (node (ref "IC4") (pin "E21") (pinfunction "IO_L23P_T3_16_E21") (pintype "bidirectional"))
    )
    (net (code "196") (name "/EXT10.LVDS_0_N") (class "Default")
      (node (ref "IC4") (pin "V14") (pinfunction "IO_L13N_T2_MRCC_13_V14") (pintype "bidirectional"))
    )
    (net (code "197") (name "/EXT10.LVDS_0_P") (class "Default")
      (node (ref "IC4") (pin "V13") (pinfunction "IO_L13P_T2_MRCC_13_V13") (pintype "bidirectional"))
    )
    (net (code "198") (name "/EXT10.LVDS_1_N") (class "Default")
      (node (ref "IC4") (pin "AA16") (pinfunction "IO_L1N_T0_13_AA16") (pintype "bidirectional"))
    )
    (net (code "199") (name "/EXT10.LVDS_1_P") (class "Default")
      (node (ref "IC4") (pin "Y16") (pinfunction "IO_L1P_T0_13_Y16") (pintype "bidirectional"))
    )
    (net (code "200") (name "/EXT10.LVDS_2_N") (class "Default")
      (node (ref "IC4") (pin "AB17") (pinfunction "IO_L2N_T0_13_AB17") (pintype "bidirectional"))
    )
    (net (code "201") (name "/EXT10.LVDS_2_P") (class "Default")
      (node (ref "IC4") (pin "AB16") (pinfunction "IO_L2P_T0_13_AB16") (pintype "bidirectional"))
    )
    (net (code "202") (name "/EXT10.LVDS_3_N") (class "Default")
      (node (ref "IC4") (pin "AB13") (pinfunction "IO_L3N_T0_DQS_13_AB13") (pintype "bidirectional"))
    )
    (net (code "203") (name "/EXT10.LVDS_3_P") (class "Default")
      (node (ref "IC4") (pin "AA13") (pinfunction "IO_L3P_T0_DQS_13_AA13") (pintype "bidirectional"))
    )
    (net (code "204") (name "/EXT10.LVDS_4_N") (class "Default")
      (node (ref "IC4") (pin "AA14") (pinfunction "IO_L5N_T0_13_AA14") (pintype "bidirectional"))
    )
    (net (code "205") (name "/EXT10.LVDS_4_P") (class "Default")
      (node (ref "IC4") (pin "Y13") (pinfunction "IO_L5P_T0_13_Y13") (pintype "bidirectional"))
    )
    (net (code "206") (name "/EXT10.LVDS_5_N") (class "Default")
      (node (ref "IC4") (pin "AB15") (pinfunction "IO_L4N_T0_13_AB15") (pintype "bidirectional"))
    )
    (net (code "207") (name "/EXT10.LVDS_5_P") (class "Default")
      (node (ref "IC4") (pin "AA15") (pinfunction "IO_L4P_T0_13_AA15") (pintype "bidirectional"))
    )
    (net (code "208") (name "/EXT10.LVDS_6_N") (class "Default")
      (node (ref "IC4") (pin "W16") (pinfunction "IO_L16N_T2_13_W16") (pintype "bidirectional"))
    )
    (net (code "209") (name "/EXT10.LVDS_6_P") (class "Default")
      (node (ref "IC4") (pin "W15") (pinfunction "IO_L16P_T2_13_W15") (pintype "bidirectional"))
    )
    (net (code "210") (name "/EXT10.LVDS_7_N") (class "Default")
      (node (ref "IC4") (pin "T15") (pinfunction "IO_L15N_T2_DQS_13_T15") (pintype "bidirectional"))
    )
    (net (code "211") (name "/EXT10.LVDS_7_P") (class "Default")
      (node (ref "IC4") (pin "T14") (pinfunction "IO_L15P_T2_DQS_13_T14") (pintype "bidirectional"))
    )
    (net (code "213") (name "/EXT11.LVDS_0_N") (class "Default")
      (node (ref "IC4") (pin "W12") (pinfunction "IO_L12N_T1_MRCC_13_W12") (pintype "bidirectional"))
    )
    (net (code "214") (name "/EXT11.LVDS_0_P") (class "Default")
      (node (ref "IC4") (pin "W11") (pinfunction "IO_L12P_T1_MRCC_13_W11") (pintype "bidirectional"))
    )
    (net (code "215") (name "/EXT11.LVDS_1_N") (class "Default")
      (node (ref "IC4") (pin "V15") (pinfunction "IO_L14N_T2_SRCC_13_V15") (pintype "bidirectional"))
    )
    (net (code "216") (name "/EXT11.LVDS_1_P") (class "Default")
      (node (ref "IC4") (pin "U15") (pinfunction "IO_L14P_T2_SRCC_13_U15") (pintype "bidirectional"))
    )
    (net (code "217") (name "/EXT11.LVDS_2_N") (class "Default")
      (node (ref "IC4") (pin "Y14") (pinfunction "IO_L6N_T0_VREF_13_Y14") (pintype "bidirectional"))
    )
    (net (code "218") (name "/EXT11.LVDS_2_P") (class "Default")
      (node (ref "IC4") (pin "W14") (pinfunction "IO_L6P_T0_13_W14") (pintype "bidirectional"))
    )
    (net (code "219") (name "/EXT11.LVDS_3_N") (class "Default")
      (node (ref "IC4") (pin "W10") (pinfunction "IO_L10N_T1_13_W10") (pintype "bidirectional"))
    )
    (net (code "220") (name "/EXT11.LVDS_3_P") (class "Default")
      (node (ref "IC4") (pin "V10") (pinfunction "IO_L10P_T1_13_V10") (pintype "bidirectional"))
    )
    (net (code "221") (name "/EXT11.LVDS_4_N") (class "Default")
      (node (ref "IC4") (pin "Y12") (pinfunction "IO_L11N_T1_SRCC_13_Y12") (pintype "bidirectional"))
    )
    (net (code "222") (name "/EXT11.LVDS_4_P") (class "Default")
      (node (ref "IC4") (pin "Y11") (pinfunction "IO_L11P_T1_SRCC_13_Y11") (pintype "bidirectional"))
    )
    (net (code "223") (name "/EXT11.LVDS_5_N") (class "Default")
      (node (ref "IC4") (pin "AB12") (pinfunction "IO_L7N_T1_13_AB12") (pintype "bidirectional"))
    )
    (net (code "224") (name "/EXT11.LVDS_5_P") (class "Default")
      (node (ref "IC4") (pin "AB11") (pinfunction "IO_L7P_T1_13_AB11") (pintype "bidirectional"))
    )
    (net (code "225") (name "/EXT11.LVDS_6_N") (class "Default")
      (node (ref "IC4") (pin "AA11") (pinfunction "IO_L9N_T1_DQS_13_AA11") (pintype "bidirectional"))
    )
    (net (code "226") (name "/EXT11.LVDS_6_P") (class "Default")
      (node (ref "IC4") (pin "AA10") (pinfunction "IO_L9P_T1_DQS_13_AA10") (pintype "bidirectional"))
    )
    (net (code "227") (name "/EXT11.LVDS_7_N") (class "Default")
      (node (ref "IC4") (pin "AB10") (pinfunction "IO_L8N_T1_13_AB10") (pintype "bidirectional"))
    )
    (net (code "228") (name "/EXT11.LVDS_7_P") (class "Default")
      (node (ref "IC4") (pin "AA9") (pinfunction "IO_L8P_T1_13_AA9") (pintype "bidirectional"))
    )
    (net (code "230") (name "/I2C_SW_SCL") (class "Default")
      (node (ref "IC4") (pin "J16") (pinfunction "IO_0_15_J16") (pintype "bidirectional"))
    )
    (net (code "231") (name "/I2C_SW_SDA") (class "Default")
      (node (ref "IC4") (pin "F15") (pinfunction "IO_0_16_F15") (pintype "bidirectional"))
    )
    (net (code "232") (name "/LED_USER1") (class "Default")
      (node (ref "IC4") (pin "N17") (pinfunction "IO_L21P_T3_DQS_14_N17") (pintype "bidirectional"))
      (node (ref "R45") (pin "2") (pinfunction "2_2") (pintype "passive"))
      (node (ref "T3") (pin "1") (pinfunction "G_1") (pintype "passive"))
    )
    (net (code "233") (name "/LED_USER2") (class "Default")
      (node (ref "IC4") (pin "V22") (pinfunction "IO_L3N_T0_DQS_EMCCLK_14_V22") (pintype "bidirectional"))
      (node (ref "R19") (pin "2") (pinfunction "2_2") (pintype "passive"))
      (node (ref "T2") (pin "1") (pinfunction "G_1") (pintype "passive"))
    )
    (net (code "234") (name "/LED_USER3") (class "Default")
      (node (ref "IC4") (pin "T21") (pinfunction "IO_L4P_T0_D04_14_T21") (pintype "bidirectional"))
      (node (ref "R23") (pin "2") (pinfunction "2_2") (pintype "passive"))
      (node (ref "T12") (pin "1") (pinfunction "G_1") (pintype "passive"))
    )
    (net (code "235") (name "/RxD_2V5") (class "Default")
      (node (ref "IC4") (pin "T16") (pinfunction "IO_L17P_T2_13_T16") (pintype "bidirectional"))
    )
    (net (code "236") (name "/SFP_0.LED") (class "Default")
      (node (ref "IC4") (pin "U16") (pinfunction "IO_L17N_T2_13_U16") (pintype "bidirectional"))
    )
    (net (code "237") (name "/SFP_0.LOS") (class "Default")
      (node (ref "IC4") (pin "N15") (pinfunction "IO_25_14_N15") (pintype "bidirectional"))
    )
    (net (code "238") (name "/SFP_0.MOD_PRESENT") (class "Default")
      (node (ref "IC4") (pin "P16") (pinfunction "IO_L24P_T3_A01_D17_14_P16") (pintype "bidirectional"))
    )
    (net (code "239") (name "/SFP_0.RATE_SELECT") (class "Default")
      (node (ref "IC4") (pin "R14") (pinfunction "IO_L19N_T3_A09_D25_VREF_14_R14") (pintype "bidirectional"))
    )
    (net (code "240") (name "/SFP_0.RATE_SELECT1") (class "Default")
      (node (ref "IC4") (pin "P15") (pinfunction "IO_L22P_T3_A05_D21_14_P15") (pintype "bidirectional"))
    )
    (net (code "241") (name "/SFP_0.TX_DISABLE") (class "Default")
      (node (ref "IC4") (pin "N14") (pinfunction "IO_L23N_T3_A02_D18_14_N14") (pintype "bidirectional"))
    )
    (net (code "242") (name "/SFP_0.TX_FAULT") (class "Default")
      (node (ref "IC4") (pin "U7") (pinfunction "IO_25_34_U7") (pintype "bidirectional"))
    )
    (net (code "243") (name "/SFP_1.LED") (class "Default")
      (node (ref "IC4") (pin "R19") (pinfunction "IO_L5N_T0_D07_14_R19") (pintype "bidirectional"))
    )
    (net (code "244") (name "/SFP_1.LOS") (class "Default")
      (node (ref "IC4") (pin "T18") (pinfunction "IO_L20N_T3_A07_D23_14_T18") (pintype "bidirectional"))
    )
    (net (code "245") (name "/SFP_1.MOD_PRESENT") (class "Default")
      (node (ref "IC4") (pin "P17") (pinfunction "IO_L21N_T3_DQS_A06_D22_14_P17") (pintype "bidirectional"))
    )
    (net (code "246") (name "/SFP_1.RATE_SELECT") (class "Default")
      (node (ref "IC4") (pin "U18") (pinfunction "IO_L18N_T2_A11_D27_14_U18") (pintype "bidirectional"))
    )
    (net (code "247") (name "/SFP_1.RATE_SELECT1") (class "Default")
      (node (ref "IC4") (pin "R18") (pinfunction "IO_L20P_T3_A08_D24_14_R18") (pintype "bidirectional"))
    )
    (net (code "248") (name "/SFP_1.TX_DISABLE") (class "Default")
      (node (ref "IC4") (pin "R17") (pinfunction "IO_L24N_T3_A00_D16_14_R17") (pintype "bidirectional"))
    )
    (net (code "249") (name "/SFP_1.TX_FAULT") (class "Default")
      (node (ref "IC4") (pin "U17") (pinfunction "IO_L18P_T2_A12_D28_14_U17") (pintype "bidirectional"))
    )
    (net (code "250") (name "/SFP_2.LED") (class "Default")
      (node (ref "IC4") (pin "W20") (pinfunction "IO_L12N_T1_MRCC_14_W20") (pintype "bidirectional"))
    )
    (net (code "251") (name "/SFP_2.LOS") (class "Default")
      (node (ref "IC4") (pin "R16") (pinfunction "IO_L22N_T3_A04_D20_14_R16") (pintype "bidirectional"))
    )
    (net (code "252") (name "/SFP_2.MOD_PRESENT") (class "Default")
      (node (ref "IC4") (pin "T20") (pinfunction "IO_L6N_T0_D08_VREF_14_T20") (pintype "bidirectional"))
    )
    (net (code "253") (name "/SFP_2.RATE_SELECT") (class "Default")
      (node (ref "IC4") (pin "P14") (pinfunction "IO_L19P_T3_A10_D26_14_P14") (pintype "bidirectional"))
    )
    (net (code "254") (name "/SFP_2.RATE_SELECT1") (class "Default")
      (node (ref "IC4") (pin "U21") (pinfunction "IO_L4N_T0_D05_14_U21") (pintype "bidirectional"))
    )
    (net (code "255") (name "/SFP_2.TX_DISABLE") (class "Default")
      (node (ref "IC4") (pin "P20") (pinfunction "IO_0_14_P20") (pintype "bidirectional"))
    )
    (net (code "256") (name "/SFP_2.TX_FAULT") (class "Default")
      (node (ref "IC4") (pin "P19") (pinfunction "IO_L5P_T0_D06_14_P19") (pintype "bidirectional"))
    )
    (net (code "257") (name "/TxD_2V5") (class "Default")
      (node (ref "IC4") (pin "M17") (pinfunction "IO_25_15_M17") (pintype "bidirectional"))
    )
    (net (code "258") (name "/VUSB_PRESENT_2V5") (class "Default")
      (node (ref "IC4") (pin "N13") (pinfunction "IO_L23P_T3_A03_D19_14_N13") (pintype "bidirectional"))
    )
    (net (code "262") (name "GND") (class "Default")
      (node (ref "R19") (pin "1") (pinfunction "1_1") (pintype "passive"))
      (node (ref "R23") (pin "1") (pinfunction "1_1") (pintype "passive"))
      (node (ref "R43") (pin "1") (pinfunction "1_1") (pintype "passive"))
      (node (ref "R45") (pin "1") (pinfunction "1_1") (pintype "passive"))
      (node (ref "T12") (pin "2") (pinfunction "S_2") (pintype "passive"))
      (node (ref "T2") (pin "2") (pinfunction "S_2") (pintype "passive"))
      (node (ref "T3") (pin "2") (pinfunction "S_2") (pintype "passive"))
    )
    (net (code "263") (name "Net-(LD2-A)") (class "Default")
      (node (ref "LD2") (pin "1") (pinfunction "A_1") (pintype "passive"))
      (node (ref "R44") (pin "1") (pinfunction "1_1") (pintype "passive"))
    )
    (net (code "264") (name "Net-(LD2-C)") (class "Default")
      (node (ref "LD2") (pin "2") (pinfunction "C_2") (pintype "passive"))
      (node (ref "T3") (pin "3") (pinfunction "D_3") (pintype "passive"))
    )
    (net (code "265") (name "Net-(LD13-A)") (class "Default")
      (node (ref "LD13") (pin "1") (pinfunction "A_1") (pintype "passive"))
      (node (ref "R11") (pin "1") (pinfunction "1_1") (pintype "passive"))
    )
    (net (code "266") (name "Net-(LD13-C)") (class "Default")
      (node (ref "LD13") (pin "2") (pinfunction "C_2") (pintype "passive"))
      (node (ref "T2") (pin "3") (pinfunction "D_3") (pintype "passive"))
    )
    (net (code "267") (name "Net-(LD14-A)") (class "Default")
      (node (ref "LD14") (pin "1") (pinfunction "A_1") (pintype "passive"))
      (node (ref "R20") (pin "1") (pinfunction "1_1") (pintype "passive"))
    )
    (net (code "268") (name "Net-(LD14-C)") (class "Default")
      (node (ref "LD14") (pin "2") (pinfunction "C_2") (pintype "passive"))
      (node (ref "T12") (pin "3") (pinfunction "D_3") (pintype "passive"))
    )
    (net (code "269") (name "P2V5") (class "Default")
      (node (ref "R42") (pin "2") (pinfunction "2_2") (pintype "passive"))
    )
    (net (code "270") (name "P3V3") (class "Default")
      (node (ref "R11") (pin "2") (pinfunction "2_2") (pintype "passive"))
      (node (ref "R20") (pin "2") (pinfunction "2_2") (pintype "passive"))
      (node (ref "R44") (pin "2") (pinfunction "2_2") (pintype "passive"))
    )
    (net (code "271") (name "unconnected-(IC4A-IO_0_13-PadY17)") (class "Default")
      (node (ref "IC4") (pin "Y17") (pinfunction "IO_0_13_Y17") (pintype "bidirectional"))
    )
    (net (code "272") (name "unconnected-(IC4B-IO_L12P_T1_MRCC_14-PadW19)") (class "Default")
      (node (ref "IC4") (pin "W19") (pinfunction "IO_L12P_T1_MRCC_14_W19") (pintype "bidirectional+no_connect"))
    )
    (net (code "273") (name "unconnected-(IC4D-IO_25_16-PadF21)") (class "Default")
      (node (ref "IC4") (pin "F21") (pinfunction "IO_25_16_F21") (pintype "bidirectional"))
    )
    (net (code "274") (name "unconnected-(IC4E-IO_0_34-PadT3)") (class "Default")
      (node (ref "IC4") (pin "T3") (pinfunction "IO_0_34_T3") (pintype "bidirectional"))
    )
  )
)
